# ed097oc4.net
KiCad netlist of a schematic drawn in EAGLE
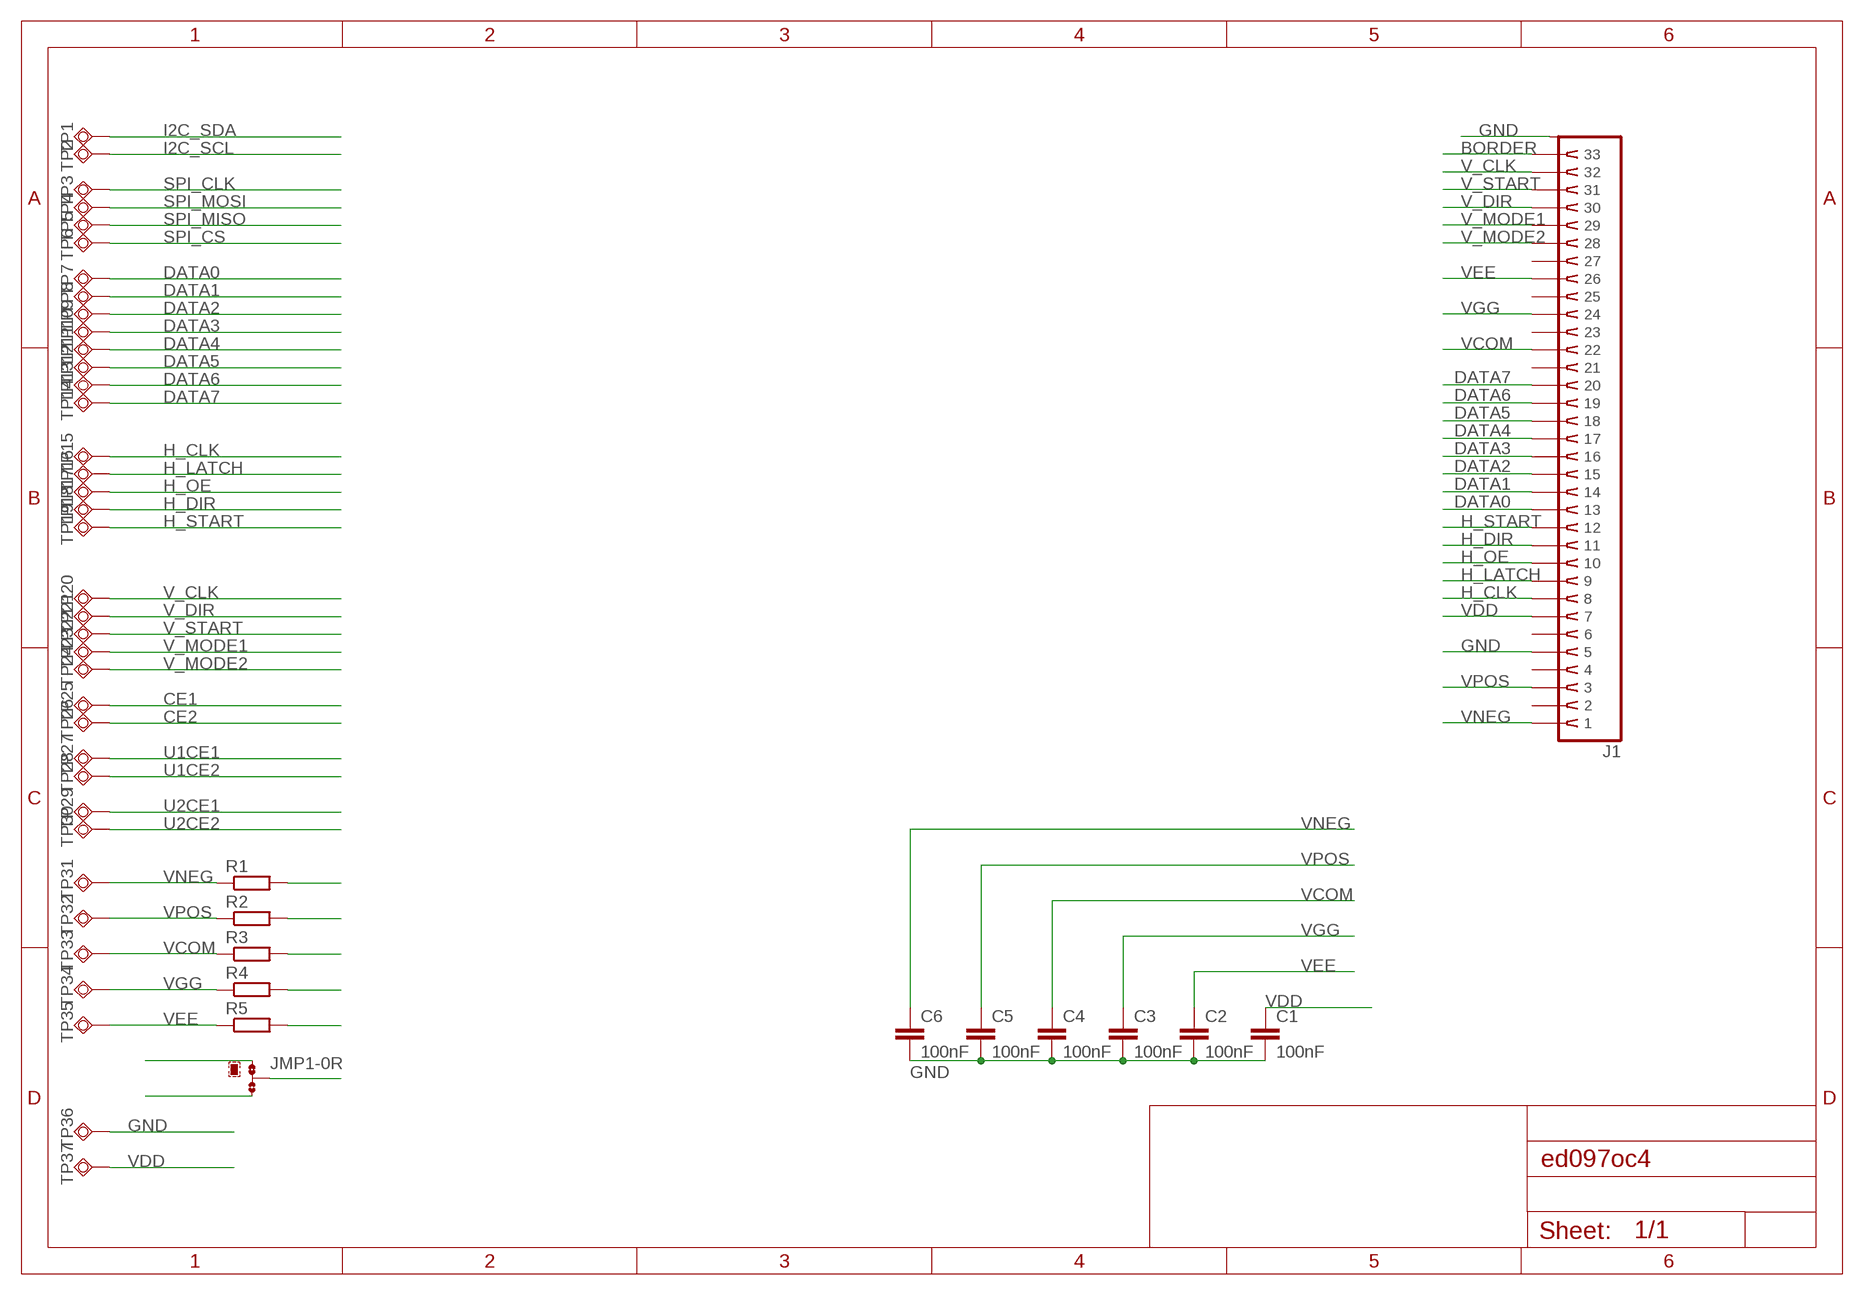
[diagram p0: schematic, sheet 1]

(export (version "E")
  (design (tool "Eeschema 10.0.6"))
  (components
    (comp (ref "C1")
      (value "100nF")
      (footprint "eagle-import:C0805")
      (libsource (lib "eagle-import") (part "C-EUC0805"))
    )
    (comp (ref "C2")
      (value "100nF")
      (footprint "eagle-import:C0805")
      (libsource (lib "eagle-import") (part "C-EUC0805"))
    )
    (comp (ref "C3")
      (value "100nF")
      (footprint "eagle-import:C0805")
      (libsource (lib "eagle-import") (part "C-EUC0805"))
    )
    (comp (ref "C4")
      (value "100nF")
      (footprint "eagle-import:C0805")
      (libsource (lib "eagle-import") (part "C-EUC0805"))
    )
    (comp (ref "C5")
      (value "100nF")
      (footprint "eagle-import:C0805")
      (libsource (lib "eagle-import") (part "C-EUC0805"))
    )
    (comp (ref "C6")
      (value "100nF")
      (footprint "eagle-import:C0805")
      (libsource (lib "eagle-import") (part "C-EUC0805"))
    )
    (comp (ref "J1")
      (value "SFV33R")
      (footprint "eagle-import:SFV33R-1STE1LF")
      (libsource (lib "eagle-import") (part "SFV33R"))
    )
    (comp (ref "JMP1")
      (value "0R-JUMPA")
      (footprint "eagle-import:A0R-JMP")
      (libsource (lib "eagle-import") (part "0R-JUMPA"))
    )
    (comp (ref "R1")
      (value "R-EU_R0805")
      (footprint "eagle-import:R0805")
      (libsource (lib "eagle-import") (part "R-EU_R0805"))
    )
    (comp (ref "R2")
      (value "R-EU_R0805")
      (footprint "eagle-import:R0805")
      (libsource (lib "eagle-import") (part "R-EU_R0805"))
    )
    (comp (ref "R3")
      (value "R-EU_R0805")
      (footprint "eagle-import:R0805")
      (libsource (lib "eagle-import") (part "R-EU_R0805"))
    )
    (comp (ref "R4")
      (value "R-EU_R0805")
      (footprint "eagle-import:R0805")
      (libsource (lib "eagle-import") (part "R-EU_R0805"))
    )
    (comp (ref "R5")
      (value "R-EU_R0805")
      (footprint "eagle-import:R0805")
      (libsource (lib "eagle-import") (part "R-EU_R0805"))
    )
    (comp (ref "TP1")
      (value "TESTPAD0.6")
      (footprint "eagle-import:VIA0.6")
      (libsource (lib "eagle-import") (part "TESTPAD0.6"))
    )
    (comp (ref "TP2")
      (value "TESTPAD0.6")
      (footprint "eagle-import:VIA0.6")
      (libsource (lib "eagle-import") (part "TESTPAD0.6"))
    )
    (comp (ref "TP3")
      (value "TESTPAD0.6")
      (footprint "eagle-import:VIA0.6")
      (libsource (lib "eagle-import") (part "TESTPAD0.6"))
    )
    (comp (ref "TP4")
      (value "TESTPAD0.6")
      (footprint "eagle-import:VIA0.6")
      (libsource (lib "eagle-import") (part "TESTPAD0.6"))
    )
    (comp (ref "TP5")
      (value "TESTPAD0.6")
      (footprint "eagle-import:VIA0.6")
      (libsource (lib "eagle-import") (part "TESTPAD0.6"))
    )
    (comp (ref "TP6")
      (value "TESTPAD0.6")
      (footprint "eagle-import:VIA0.6")
      (libsource (lib "eagle-import") (part "TESTPAD0.6"))
    )
    (comp (ref "TP7")
      (value "TESTPAD0.6")
      (footprint "eagle-import:VIA0.6")
      (libsource (lib "eagle-import") (part "TESTPAD0.6"))
    )
    (comp (ref "TP8")
      (value "TESTPAD0.6")
      (footprint "eagle-import:VIA0.6")
      (libsource (lib "eagle-import") (part "TESTPAD0.6"))
    )
    (comp (ref "TP9")
      (value "TESTPAD0.6")
      (footprint "eagle-import:VIA0.6")
      (libsource (lib "eagle-import") (part "TESTPAD0.6"))
    )
    (comp (ref "TP10")
      (value "TESTPAD0.6")
      (footprint "eagle-import:VIA0.6")
      (libsource (lib "eagle-import") (part "TESTPAD0.6"))
    )
    (comp (ref "TP11")
      (value "TESTPAD0.6")
      (footprint "eagle-import:VIA0.6")
      (libsource (lib "eagle-import") (part "TESTPAD0.6"))
    )
    (comp (ref "TP12")
      (value "TESTPAD0.6")
      (footprint "eagle-import:VIA0.6")
      (libsource (lib "eagle-import") (part "TESTPAD0.6"))
    )
    (comp (ref "TP13")
      (value "TESTPAD0.6")
      (footprint "eagle-import:VIA0.6")
      (libsource (lib "eagle-import") (part "TESTPAD0.6"))
    )
    (comp (ref "TP14")
      (value "TESTPAD0.6")
      (footprint "eagle-import:VIA0.6")
      (libsource (lib "eagle-import") (part "TESTPAD0.6"))
    )
    (comp (ref "TP15")
      (value "TESTPAD0.6")
      (footprint "eagle-import:VIA0.6")
      (libsource (lib "eagle-import") (part "TESTPAD0.6"))
    )
    (comp (ref "TP16")
      (value "TESTPAD0.6")
      (footprint "eagle-import:VIA0.6")
      (libsource (lib "eagle-import") (part "TESTPAD0.6"))
    )
    (comp (ref "TP17")
      (value "TESTPAD0.6")
      (footprint "eagle-import:VIA0.6")
      (libsource (lib "eagle-import") (part "TESTPAD0.6"))
    )
    (comp (ref "TP18")
      (value "TESTPAD0.6")
      (footprint "eagle-import:VIA0.6")
      (libsource (lib "eagle-import") (part "TESTPAD0.6"))
    )
    (comp (ref "TP19")
      (value "TESTPAD0.6")
      (footprint "eagle-import:VIA0.6")
      (libsource (lib "eagle-import") (part "TESTPAD0.6"))
    )
    (comp (ref "TP20")
      (value "TESTPAD0.6")
      (footprint "eagle-import:VIA0.6")
      (libsource (lib "eagle-import") (part "TESTPAD0.6"))
    )
    (comp (ref "TP21")
      (value "TESTPAD0.6")
      (footprint "eagle-import:VIA0.6")
      (libsource (lib "eagle-import") (part "TESTPAD0.6"))
    )
    (comp (ref "TP22")
      (value "TESTPAD0.6")
      (footprint "eagle-import:VIA0.6")
      (libsource (lib "eagle-import") (part "TESTPAD0.6"))
    )
    (comp (ref "TP23")
      (value "TESTPAD0.6")
      (footprint "eagle-import:VIA0.6")
      (libsource (lib "eagle-import") (part "TESTPAD0.6"))
    )
    (comp (ref "TP24")
      (value "TESTPAD0.6")
      (footprint "eagle-import:VIA0.6")
      (libsource (lib "eagle-import") (part "TESTPAD0.6"))
    )
    (comp (ref "TP25")
      (value "TESTPAD0.6")
      (footprint "eagle-import:VIA0.6")
      (libsource (lib "eagle-import") (part "TESTPAD0.6"))
    )
    (comp (ref "TP26")
      (value "TESTPAD0.6")
      (footprint "eagle-import:VIA0.6")
      (libsource (lib "eagle-import") (part "TESTPAD0.6"))
    )
    (comp (ref "TP27")
      (value "TESTPAD0.6")
      (footprint "eagle-import:VIA0.6")
      (libsource (lib "eagle-import") (part "TESTPAD0.6"))
    )
    (comp (ref "TP28")
      (value "TESTPAD0.6")
      (footprint "eagle-import:VIA0.6")
      (libsource (lib "eagle-import") (part "TESTPAD0.6"))
    )
    (comp (ref "TP29")
      (value "TESTPAD0.6")
      (footprint "eagle-import:VIA0.6")
      (libsource (lib "eagle-import") (part "TESTPAD0.6"))
    )
    (comp (ref "TP30")
      (value "TESTPAD0.6")
      (footprint "eagle-import:VIA0.6")
      (libsource (lib "eagle-import") (part "TESTPAD0.6"))
    )
    (comp (ref "TP31")
      (value "TESTPAD0.6")
      (footprint "eagle-import:VIA0.6")
      (libsource (lib "eagle-import") (part "TESTPAD0.6"))
    )
    (comp (ref "TP32")
      (value "TESTPAD0.6")
      (footprint "eagle-import:VIA0.6")
      (libsource (lib "eagle-import") (part "TESTPAD0.6"))
    )
    (comp (ref "TP33")
      (value "TESTPAD0.6")
      (footprint "eagle-import:VIA0.6")
      (libsource (lib "eagle-import") (part "TESTPAD0.6"))
    )
    (comp (ref "TP34")
      (value "TESTPAD0.6")
      (footprint "eagle-import:VIA0.6")
      (libsource (lib "eagle-import") (part "TESTPAD0.6"))
    )
    (comp (ref "TP35")
      (value "TESTPAD0.6")
      (footprint "eagle-import:VIA0.6")
      (libsource (lib "eagle-import") (part "TESTPAD0.6"))
    )
    (comp (ref "TP36")
      (value "TESTPAD0.6")
      (footprint "eagle-import:VIA0.6")
      (libsource (lib "eagle-import") (part "TESTPAD0.6"))
    )
    (comp (ref "TP37")
      (value "TESTPAD0.6")
      (footprint "eagle-import:VIA0.6")
      (libsource (lib "eagle-import") (part "TESTPAD0.6"))
    )
  )
  (nets
    (net (code "1") (name "/BORDER") (class "Default")
      (node (ref "J1") (pin "33") (pinfunction "33_33") (pintype "passive"))
    )
    (net (code "2") (name "/CE1") (class "Default")
      (node (ref "TP25") (pin "P$1") (pinfunction "TP_P$1") (pintype "input"))
    )
    (net (code "3") (name "/CE2") (class "Default")
      (node (ref "TP26") (pin "P$1") (pinfunction "TP_P$1") (pintype "input"))
    )
    (net (code "4") (name "/DATA0") (class "Default")
      (node (ref "J1") (pin "13") (pinfunction "13_13") (pintype "passive"))
      (node (ref "TP7") (pin "P$1") (pinfunction "TP_P$1") (pintype "input"))
    )
    (net (code "5") (name "/DATA1") (class "Default")
      (node (ref "J1") (pin "14") (pinfunction "14_14") (pintype "passive"))
      (node (ref "TP8") (pin "P$1") (pinfunction "TP_P$1") (pintype "input"))
    )
    (net (code "6") (name "/DATA2") (class "Default")
      (node (ref "J1") (pin "15") (pinfunction "15_15") (pintype "passive"))
      (node (ref "TP9") (pin "P$1") (pinfunction "TP_P$1") (pintype "input"))
    )
    (net (code "7") (name "/DATA3") (class "Default")
      (node (ref "J1") (pin "16") (pinfunction "16_16") (pintype "passive"))
      (node (ref "TP10") (pin "P$1") (pinfunction "TP_P$1") (pintype "input"))
    )
    (net (code "8") (name "/DATA4") (class "Default")
      (node (ref "J1") (pin "17") (pinfunction "17_17") (pintype "passive"))
      (node (ref "TP11") (pin "P$1") (pinfunction "TP_P$1") (pintype "input"))
    )
    (net (code "9") (name "/DATA5") (class "Default")
      (node (ref "J1") (pin "18") (pinfunction "18_18") (pintype "passive"))
      (node (ref "TP12") (pin "P$1") (pinfunction "TP_P$1") (pintype "input"))
    )
    (net (code "10") (name "/DATA6") (class "Default")
      (node (ref "J1") (pin "19") (pinfunction "19_19") (pintype "passive"))
      (node (ref "TP13") (pin "P$1") (pinfunction "TP_P$1") (pintype "input"))
    )
    (net (code "11") (name "/DATA7") (class "Default")
      (node (ref "J1") (pin "20") (pinfunction "20_20") (pintype "passive"))
      (node (ref "TP14") (pin "P$1") (pinfunction "TP_P$1") (pintype "input"))
    )
    (net (code "12") (name "/GND") (class "Default")
      (node (ref "C1") (pin "2") (pinfunction "2_2") (pintype "passive"))
      (node (ref "C2") (pin "2") (pinfunction "2_2") (pintype "passive"))
      (node (ref "C3") (pin "2") (pinfunction "2_2") (pintype "passive"))
      (node (ref "C4") (pin "2") (pinfunction "2_2") (pintype "passive"))
      (node (ref "C5") (pin "2") (pinfunction "2_2") (pintype "passive"))
      (node (ref "C6") (pin "2") (pinfunction "2_2") (pintype "passive"))
      (node (ref "J1") (pin "5") (pinfunction "5_5") (pintype "passive"))
      (node (ref "J1") (pin "SHLD1") (pinfunction "SHLD_SHLD1") (pintype "power_in"))
      (node (ref "J1") (pin "SHLD2") (pinfunction "SHLD_SHLD2") (pintype "power_in"))
      (node (ref "TP36") (pin "P$1") (pinfunction "TP_P$1") (pintype "input"))
    )
    (net (code "13") (name "/H_CLK") (class "Default")
      (node (ref "J1") (pin "8") (pinfunction "8_8") (pintype "passive"))
      (node (ref "TP15") (pin "P$1") (pinfunction "TP_P$1") (pintype "input"))
    )
    (net (code "14") (name "/H_DIR") (class "Default")
      (node (ref "J1") (pin "11") (pinfunction "11_11") (pintype "passive"))
      (node (ref "TP18") (pin "P$1") (pinfunction "TP_P$1") (pintype "input"))
    )
    (net (code "15") (name "/H_LATCH") (class "Default")
      (node (ref "J1") (pin "9") (pinfunction "9_9") (pintype "passive"))
      (node (ref "TP16") (pin "P$1") (pinfunction "TP_P$1") (pintype "input"))
    )
    (net (code "16") (name "/H_OE") (class "Default")
      (node (ref "J1") (pin "10") (pinfunction "10_10") (pintype "passive"))
      (node (ref "TP17") (pin "P$1") (pinfunction "TP_P$1") (pintype "input"))
    )
    (net (code "17") (name "/H_START") (class "Default")
      (node (ref "J1") (pin "12") (pinfunction "12_12") (pintype "passive"))
      (node (ref "TP19") (pin "P$1") (pinfunction "TP_P$1") (pintype "input"))
    )
    (net (code "18") (name "/I2C_SCL") (class "Default")
      (node (ref "TP2") (pin "P$1") (pinfunction "TP_P$1") (pintype "input"))
    )
    (net (code "19") (name "/I2C_SDA") (class "Default")
      (node (ref "TP1") (pin "P$1") (pinfunction "TP_P$1") (pintype "input"))
    )
    (net (code "20") (name "/SPI_CLK") (class "Default")
      (node (ref "TP3") (pin "P$1") (pinfunction "TP_P$1") (pintype "input"))
    )
    (net (code "21") (name "/SPI_CS") (class "Default")
      (node (ref "TP6") (pin "P$1") (pinfunction "TP_P$1") (pintype "input"))
    )
    (net (code "22") (name "/SPI_MISO") (class "Default")
      (node (ref "TP5") (pin "P$1") (pinfunction "TP_P$1") (pintype "input"))
    )
    (net (code "23") (name "/SPI_MOSI") (class "Default")
      (node (ref "TP4") (pin "P$1") (pinfunction "TP_P$1") (pintype "input"))
    )
    (net (code "24") (name "/U1CE1") (class "Default")
      (node (ref "TP27") (pin "P$1") (pinfunction "TP_P$1") (pintype "input"))
    )
    (net (code "25") (name "/U1CE2") (class "Default")
      (node (ref "TP28") (pin "P$1") (pinfunction "TP_P$1") (pintype "input"))
    )
    (net (code "26") (name "/U2CE1") (class "Default")
      (node (ref "TP29") (pin "P$1") (pinfunction "TP_P$1") (pintype "input"))
    )
    (net (code "27") (name "/U2CE2") (class "Default")
      (node (ref "TP30") (pin "P$1") (pinfunction "TP_P$1") (pintype "input"))
    )
    (net (code "28") (name "/VCOM") (class "Default")
      (node (ref "C4") (pin "1") (pinfunction "1_1") (pintype "passive"))
      (node (ref "J1") (pin "22") (pinfunction "22_22") (pintype "passive"))
      (node (ref "R3") (pin "1") (pinfunction "1_1") (pintype "passive"))
      (node (ref "TP33") (pin "P$1") (pinfunction "TP_P$1") (pintype "input"))
    )
    (net (code "29") (name "/VDD") (class "Default")
      (node (ref "C1") (pin "1") (pinfunction "1_1") (pintype "passive"))
      (node (ref "J1") (pin "7") (pinfunction "7_7") (pintype "passive"))
      (node (ref "TP37") (pin "P$1") (pinfunction "TP_P$1") (pintype "input"))
    )
    (net (code "30") (name "/VEE") (class "Default")
      (node (ref "C2") (pin "1") (pinfunction "1_1") (pintype "passive"))
      (node (ref "J1") (pin "26") (pinfunction "26_26") (pintype "passive"))
      (node (ref "R5") (pin "1") (pinfunction "1_1") (pintype "passive"))
      (node (ref "TP35") (pin "P$1") (pinfunction "TP_P$1") (pintype "input"))
    )
    (net (code "31") (name "/VGG") (class "Default")
      (node (ref "C3") (pin "1") (pinfunction "1_1") (pintype "passive"))
      (node (ref "J1") (pin "24") (pinfunction "24_24") (pintype "passive"))
      (node (ref "R4") (pin "1") (pinfunction "1_1") (pintype "passive"))
      (node (ref "TP34") (pin "P$1") (pinfunction "TP_P$1") (pintype "input"))
    )
    (net (code "32") (name "/VNEG") (class "Default")
      (node (ref "C6") (pin "1") (pinfunction "1_1") (pintype "passive"))
      (node (ref "J1") (pin "1") (pinfunction "1_1") (pintype "passive"))
      (node (ref "R1") (pin "1") (pinfunction "1_1") (pintype "passive"))
      (node (ref "TP31") (pin "P$1") (pinfunction "TP_P$1") (pintype "input"))
    )
    (net (code "33") (name "/VPOS") (class "Default")
      (node (ref "C5") (pin "1") (pinfunction "1_1") (pintype "passive"))
      (node (ref "J1") (pin "3") (pinfunction "3_3") (pintype "passive"))
      (node (ref "R2") (pin "1") (pinfunction "1_1") (pintype "passive"))
      (node (ref "TP32") (pin "P$1") (pinfunction "TP_P$1") (pintype "input"))
    )
    (net (code "34") (name "/V_CLK") (class "Default")
      (node (ref "J1") (pin "32") (pinfunction "32_32") (pintype "passive"))
      (node (ref "TP20") (pin "P$1") (pinfunction "TP_P$1") (pintype "input"))
    )
    (net (code "35") (name "/V_DIR") (class "Default")
      (node (ref "J1") (pin "30") (pinfunction "30_30") (pintype "passive"))
      (node (ref "TP21") (pin "P$1") (pinfunction "TP_P$1") (pintype "input"))
    )
    (net (code "36") (name "/V_MODE1") (class "Default")
      (node (ref "J1") (pin "29") (pinfunction "29_29") (pintype "passive"))
      (node (ref "TP23") (pin "P$1") (pinfunction "TP_P$1") (pintype "input"))
    )
    (net (code "37") (name "/V_MODE2") (class "Default")
      (node (ref "J1") (pin "28") (pinfunction "28_28") (pintype "passive"))
      (node (ref "TP24") (pin "P$1") (pinfunction "TP_P$1") (pintype "input"))
    )
    (net (code "38") (name "/V_START") (class "Default")
      (node (ref "J1") (pin "31") (pinfunction "31_31") (pintype "passive"))
      (node (ref "TP22") (pin "P$1") (pinfunction "TP_P$1") (pintype "input"))
    )
    (net (code "39") (name "unconnected-(J1-Pad2)") (class "Default")
      (node (ref "J1") (pin "2") (pinfunction "2_2") (pintype "passive"))
    )
    (net (code "40") (name "unconnected-(J1-Pad4)") (class "Default")
      (node (ref "J1") (pin "4") (pinfunction "4_4") (pintype "passive"))
    )
    (net (code "41") (name "unconnected-(J1-Pad6)") (class "Default")
      (node (ref "J1") (pin "6") (pinfunction "6_6") (pintype "passive"))
    )
    (net (code "42") (name "unconnected-(J1-Pad21)") (class "Default")
      (node (ref "J1") (pin "21") (pinfunction "21_21") (pintype "passive"))
    )
    (net (code "43") (name "unconnected-(J1-Pad23)") (class "Default")
      (node (ref "J1") (pin "23") (pinfunction "23_23") (pintype "passive"))
    )
    (net (code "44") (name "unconnected-(J1-Pad25)") (class "Default")
      (node (ref "J1") (pin "25") (pinfunction "25_25") (pintype "passive"))
    )
    (net (code "45") (name "unconnected-(J1-Pad27)") (class "Default")
      (node (ref "J1") (pin "27") (pinfunction "27_27") (pintype "passive"))
    )
    (net (code "46") (name "unconnected-(JMP1-Pad1)") (class "Default")
      (node (ref "JMP1") (pin "1") (pinfunction "1_1") (pintype "passive"))
    )
    (net (code "47") (name "unconnected-(JMP1-Pad2)") (class "Default")
      (node (ref "JMP1") (pin "2") (pinfunction "2_2") (pintype "passive"))
    )
    (net (code "48") (name "unconnected-(JMP1-Pad3)") (class "Default")
      (node (ref "JMP1") (pin "3") (pinfunction "3_3") (pintype "passive"))
    )
    (net (code "49") (name "unconnected-(R1-Pad2)") (class "Default")
      (node (ref "R1") (pin "2") (pinfunction "2_2") (pintype "passive"))
    )
    (net (code "50") (name "unconnected-(R2-Pad2)") (class "Default")
      (node (ref "R2") (pin "2") (pinfunction "2_2") (pintype "passive"))
    )
    (net (code "51") (name "unconnected-(R3-Pad2)") (class "Default")
      (node (ref "R3") (pin "2") (pinfunction "2_2") (pintype "passive"))
    )
    (net (code "52") (name "unconnected-(R4-Pad2)") (class "Default")
      (node (ref "R4") (pin "2") (pinfunction "2_2") (pintype "passive"))
    )
    (net (code "53") (name "unconnected-(R5-Pad2)") (class "Default")
      (node (ref "R5") (pin "2") (pinfunction "2_2") (pintype "passive"))
    )
  )
)
